# Sheet1.net
KiCad netlist of a schematic drawn in Altium Designer
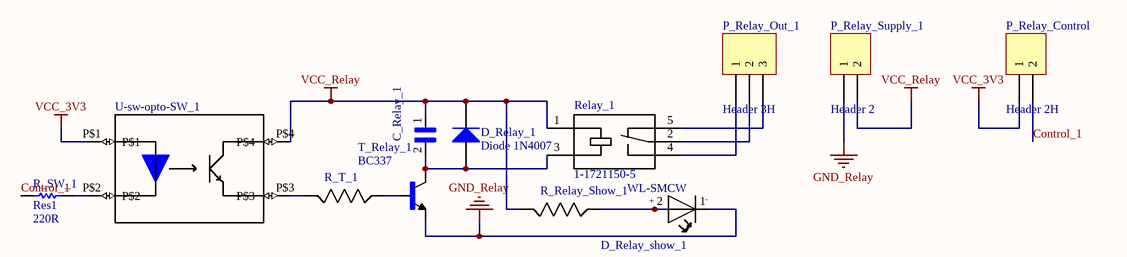
[diagram p0: Sheet1.SchDoc]

(export (version "E")
  (design (tool "Eeschema 10.0.6"))
  (components
    (comp (ref "C_Relay_1")
      (value "1206YC105KA72A")
      (footprint "CAPC3216X94N")
      (description "Cap Ceramic 1uF 16V X7R 10% SMD 1206 125Â°C Embossed T/R")
      (fields (field (name "MF") "AVX"))
      (libsource (lib "1206YC105KA72A") (part "1206YC105KA72A"))
    )
    (comp (ref "D_Relay_1")
      (value "Diode 1N4007")
      (footprint "DO-41")
      (description "1 Amp General Purpose Rectifier")
      (fields (field (name "PUBLISHER") "Altium Limited"))
      (libsource (lib "Miscellaneous Devices") (part "Diode 1N4007"))
    )
    (comp (ref "D_Relay_show_1")
      (value "WL-SMCW")
      (footprint "WL-SMCW_0603")
      (description "LED, 1206, SUP. RED, 60MCD, 630NM; Bulb Size: -; LED Colour: Red; Luminous Intensi")
      (fields (field (name "MF") "Wurth") (field (name "MP") "150120SS75000"))
      (libsource (lib "WL-SMCW") (part "WL-SMCW"))
    )
    (comp (ref "P_Relay_Control")
      (value "Header 2H")
      (footprint "HDR1X2H")
      (description "Header, 2-Pin, Right Angle")
      (fields (field (name "PUBLISHER") "Altium Limited"))
      (libsource (lib "Miscellaneous Connectors") (part "Header 2H"))
    )
    (comp (ref "P_Relay_Out_1")
      (value "Header 3H")
      (footprint "HDR1X3H")
      (description "Header, 3-Pin, Right Angle")
      (fields (field (name "PUBLISHER") "Altium Limited"))
      (libsource (lib "Miscellaneous Connectors") (part "Header 3H"))
    )
    (comp (ref "P_Relay_Supply_1")
      (value "Header 2")
      (footprint "HDR1X2")
      (description "Header, 2-Pin")
      (fields (field (name "PUBLISHER") "Altium Limited"))
      (libsource (lib "Miscellaneous Connectors") (part "Header 2"))
    )
    (comp (ref "Relay_1")
      (value "1-1721150-5")
      (footprint "TE_1-1721150-5")
      (description "General Purpose Relay, ORWH Series, Power, Non Latching, SPDT, 24 VDC, 10 A")
      (fields (field (name "MF") "TE Connectivity") (field (name "MP") "ORWH-SH-124D1F,000"))
      (libsource (lib "1-1721150-5") (part "1-1721150-5"))
    )
    (comp (ref "R_Relay_Show_1")
      (value "CRCW12061K00FKEA")
      (footprint "RESC3216X65")
      (description "Res Thick Film 1206 1K Ohm 1% 0.25W_1/4W_ Â±100ppm/C Molded SMD Automotive Paper T/R")
      (fields (field (name "MF") "Vishay"))
      (libsource (lib "CRCW12061K00FKEA") (part "CRCW12061K00FKEA"))
    )
    (comp (ref "R_SW_1")
      (value "Res1")
      (footprint "AXIAL-0.3")
      (description "Resistor")
      (fields (field (name "ALTIUM_VALUE") "220R") (field (name "PUBLISHER") "Altium Limited"))
      (libsource (lib "Miscellaneous Devices") (part "Res1"))
    )
    (comp (ref "R_T_1")
      (value "CRCW12061K00FKEA")
      (footprint "RESC3216X65")
      (description "Res Thick Film 1206 1K Ohm 1% 0.25W_1/4W_ Â±100ppm/C Molded SMD Automotive Paper T/R")
      (fields (field (name "MF") "Vishay"))
      (libsource (lib "CRCW12061K00FKEA") (part "CRCW12061K00FKEA"))
    )
    (comp (ref "T_Relay_1")
      (value "BC337")
      (footprint "TO92")
      (description "NPN Bipolar Transistor")
      (fields (field (name "MF") "ON Semiconductor"))
      (libsource (lib "BC337") (part "BC337"))
    )
    (comp (ref "U-sw-opto-SW_1")
      (value "TLP521-1")
      (footprint "TLP521-1_TLP521-1(Primary)")
      (description "4PIN DIP/PKG PHOTOCOUPLER GaAs IRED & PHOTO-TRANSISTOR")
      (fields (field (name "MF") "Toshiba"))
      (libsource (lib "TLP521-1") (part "TLP521-1"))
    )
  )
  (nets
    (net (code "1") (name "/Control_1") (class "Default")
      (node (ref "P_Relay_Control") (pin "2") (pinfunction "2_2") (pintype "passive"))
      (node (ref "R_SW_1") (pin "1") (pinfunction "1_1") (pintype "passive"))
    )
    (net (code "2") (name "GND_Relay") (class "Default")
      (node (ref "D_Relay_show_1") (pin "1") (pinfunction "NEG_1") (pintype "bidirectional"))
      (node (ref "P_Relay_Supply_1") (pin "1") (pinfunction "1_1") (pintype "passive"))
      (node (ref "T_Relay_1") (pin "1") (pinfunction "E_1") (pintype "passive"))
    )
    (net (code "3") (name "Net-(D_Relay_1-A)") (class "Default")
      (node (ref "C_Relay_1") (pin "2") (pinfunction "2_2") (pintype "passive"))
      (node (ref "D_Relay_1") (pin "1") (pinfunction "A_1") (pintype "passive"))
      (node (ref "Relay_1") (pin "3") (pinfunction "C2_3") (pintype "passive"))
      (node (ref "T_Relay_1") (pin "3") (pinfunction "C_3") (pintype "passive"))
    )
    (net (code "4") (name "Net-(D_Relay_show_1-POS)") (class "Default")
      (node (ref "D_Relay_show_1") (pin "2") (pinfunction "POS_2") (pintype "bidirectional"))
      (node (ref "R_Relay_Show_1") (pin "2") (pinfunction "2_2") (pintype "passive"))
    )
    (net (code "5") (name "Net-(R_SW_1-Pad2)") (class "Default")
      (node (ref "R_SW_1") (pin "2") (pinfunction "2_2") (pintype "passive"))
      (node (ref "U-sw-opto-SW_1") (pin "P$2") (pinfunction "P$2_P$2") (pintype "bidirectional"))
    )
    (net (code "6") (name "Net-(R_T_1-Pad1)") (class "Default")
      (node (ref "R_T_1") (pin "1") (pinfunction "1_1") (pintype "passive"))
      (node (ref "U-sw-opto-SW_1") (pin "P$3") (pinfunction "P$3_P$3") (pintype "bidirectional"))
    )
    (net (code "7") (name "Net-(Relay_1-C)") (class "Default")
      (node (ref "P_Relay_Out_1") (pin "2") (pinfunction "2_2") (pintype "passive"))
      (node (ref "Relay_1") (pin "2") (pinfunction "C_2") (pintype "passive"))
    )
    (net (code "8") (name "Net-(Relay_1-NC)") (class "Default")
      (node (ref "P_Relay_Out_1") (pin "3") (pinfunction "3_3") (pintype "passive"))
      (node (ref "Relay_1") (pin "5") (pinfunction "NC_5") (pintype "passive"))
    )
    (net (code "9") (name "Net-(Relay_1-NO)") (class "Default")
      (node (ref "P_Relay_Out_1") (pin "1") (pinfunction "1_1") (pintype "passive"))
      (node (ref "Relay_1") (pin "4") (pinfunction "NO_4") (pintype "passive"))
    )
    (net (code "10") (name "Net-(T_Relay_1-B)") (class "Default")
      (node (ref "R_T_1") (pin "2") (pinfunction "2_2") (pintype "passive"))
      (node (ref "T_Relay_1") (pin "2") (pinfunction "B_2") (pintype "passive"))
    )
    (net (code "11") (name "VCC_3V3") (class "Default")
      (node (ref "P_Relay_Control") (pin "1") (pinfunction "1_1") (pintype "passive"))
      (node (ref "U-sw-opto-SW_1") (pin "P$1") (pinfunction "P$1_P$1") (pintype "bidirectional"))
    )
    (net (code "12") (name "VCC_Relay") (class "Default")
      (node (ref "C_Relay_1") (pin "1") (pinfunction "1_1") (pintype "passive"))
      (node (ref "D_Relay_1") (pin "2") (pinfunction "K_2") (pintype "passive"))
      (node (ref "P_Relay_Supply_1") (pin "2") (pinfunction "2_2") (pintype "passive"))
      (node (ref "R_Relay_Show_1") (pin "1") (pinfunction "1_1") (pintype "passive"))
      (node (ref "Relay_1") (pin "1") (pinfunction "C1_1") (pintype "passive"))
      (node (ref "U-sw-opto-SW_1") (pin "P$4") (pinfunction "P$4_P$4") (pintype "bidirectional"))
    )
  )
)
